# SCH_Pico_funboard_core3_2025-11-06.net
KiCad netlist of a schematic drawn in EasyEDA
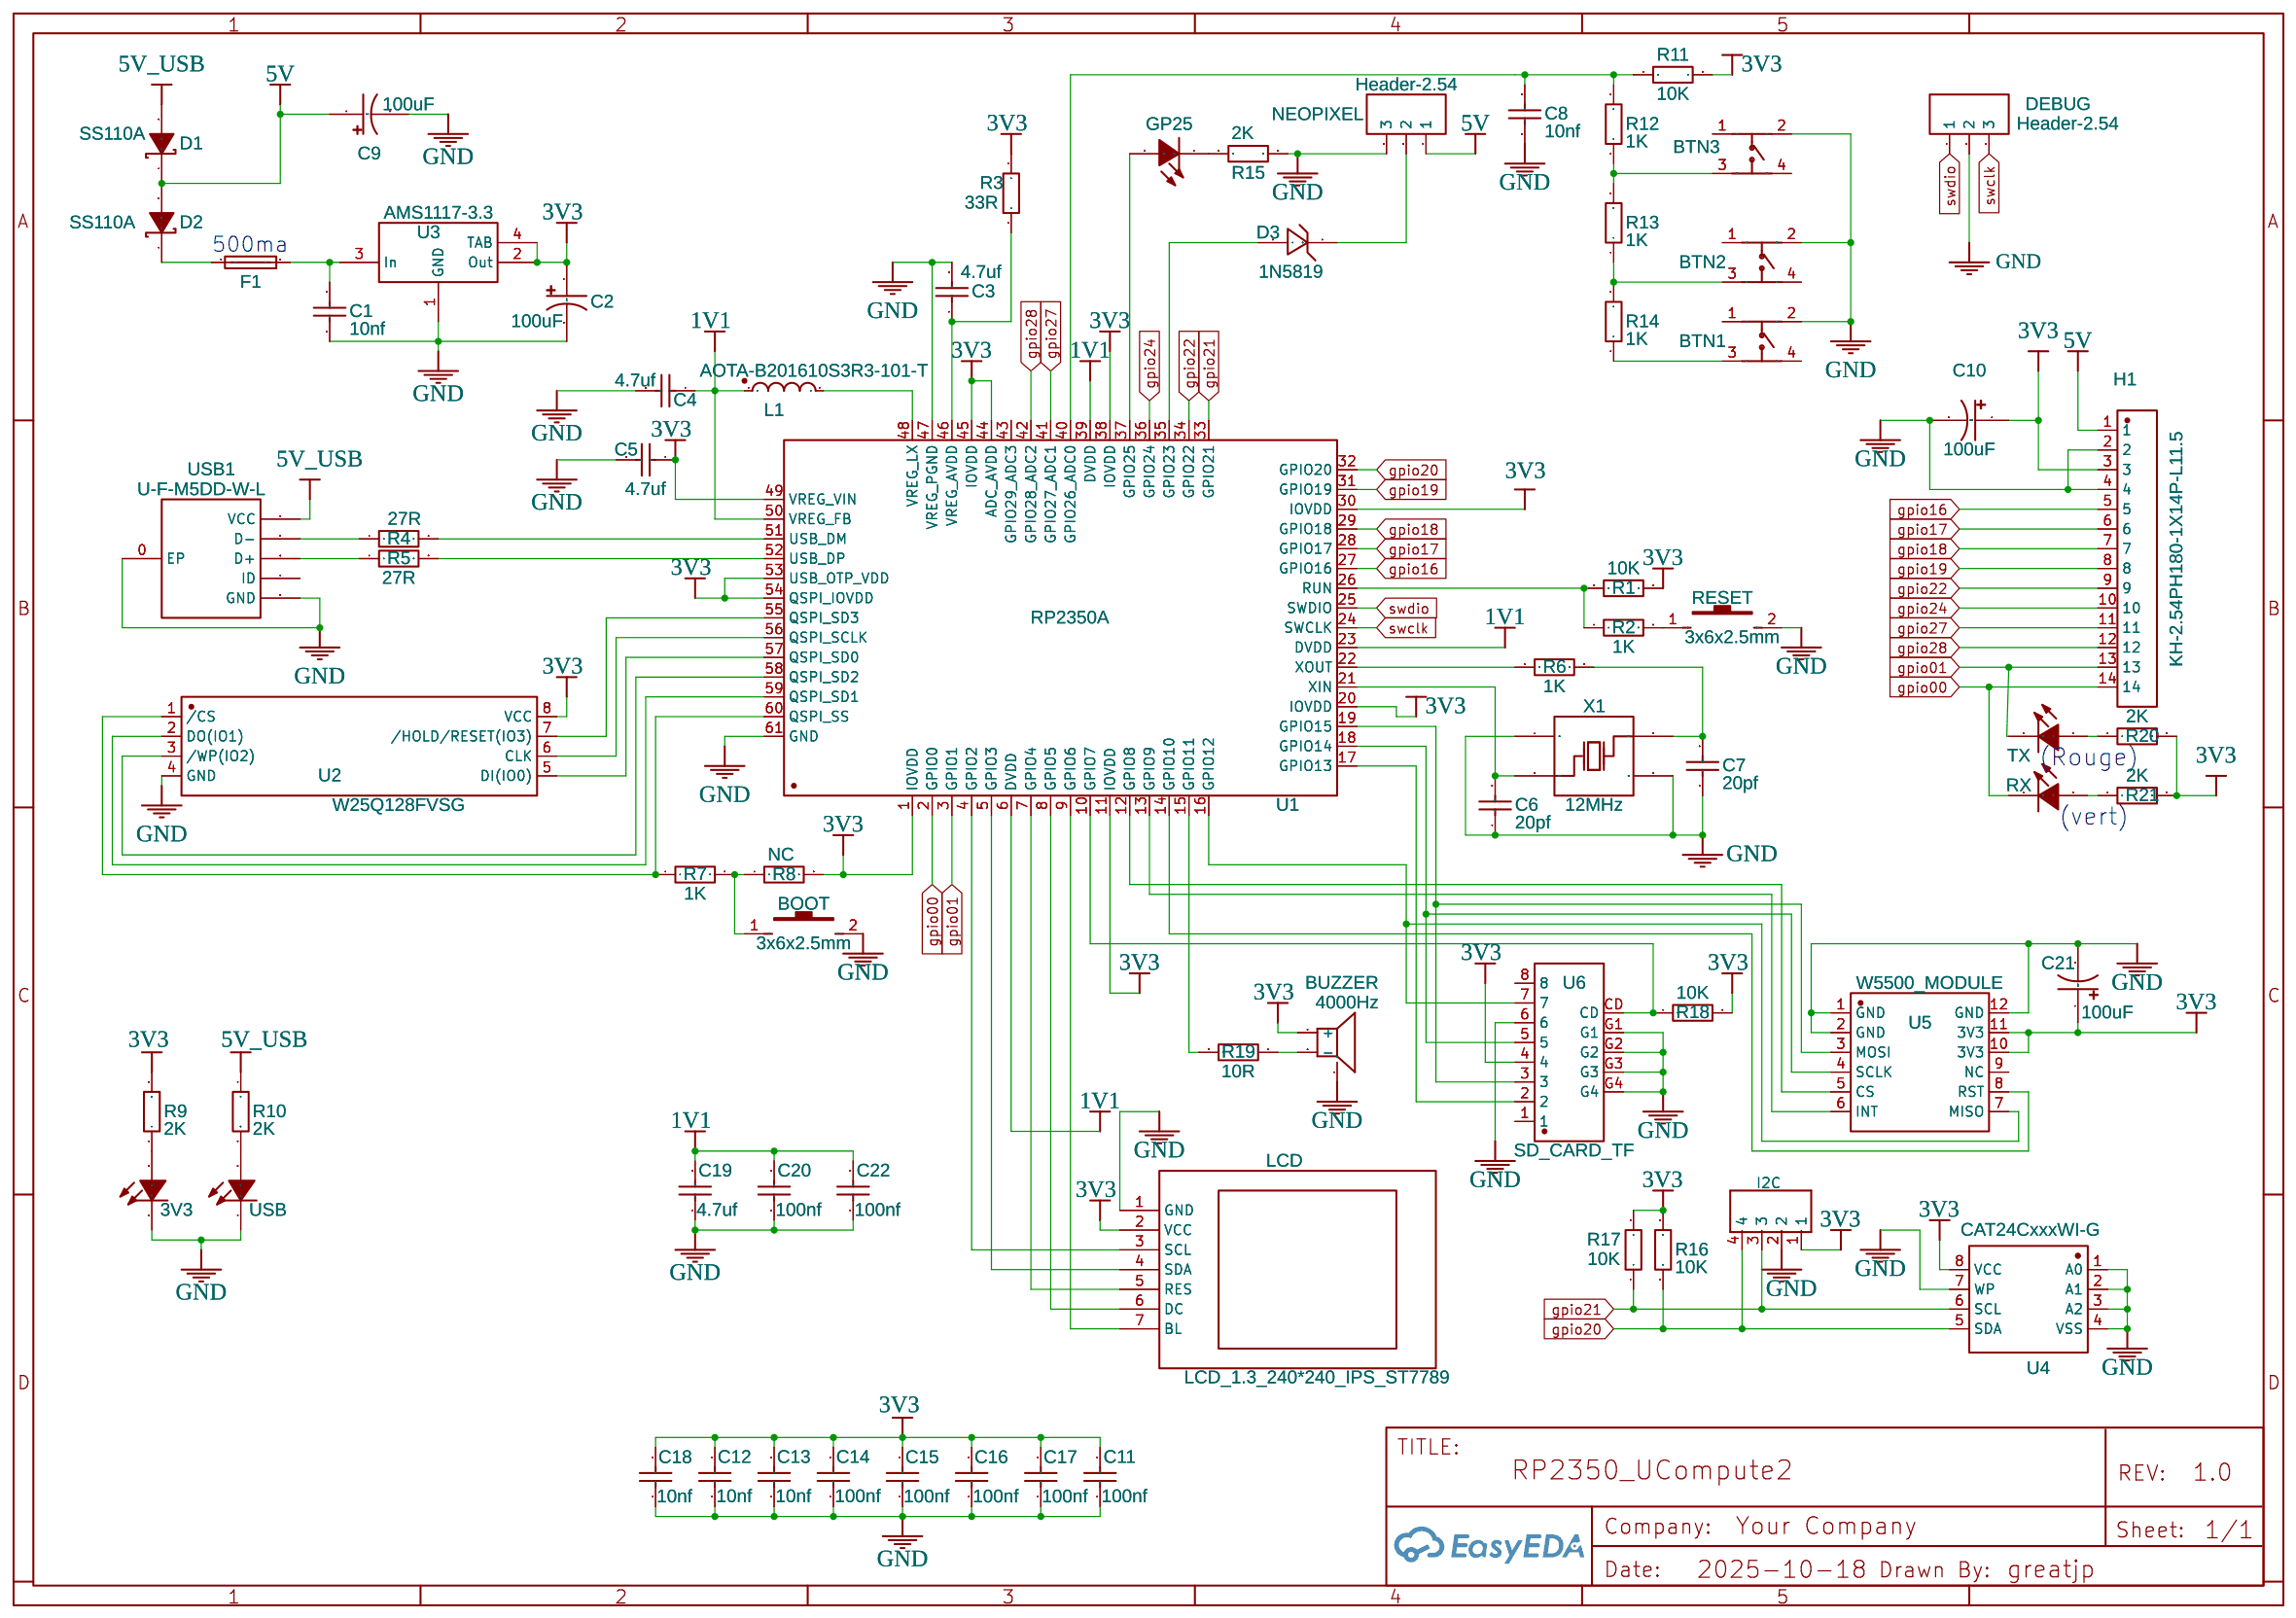
[diagram p0: schematic sheet]

(export (version "E")
  (design (tool "Eeschema 10.0.6"))
  (components
    (comp (ref "3V3")
      (value "XL-1206QPC")
      (fields (field (name "Manufacturer") "LCSC"))
      (libsource (lib "") (part "XL-1206QPC_1"))
    )
    (comp (ref "BOOT")
      (value "3x6x2.5mm")
      (fields (field (name "Manufacturer") "ReliaPro"))
      (libsource (lib "") (part "3x6x2.5mm"))
    )
    (comp (ref "BTN1")
      (value "TC-1102-A-J-R")
      (fields (field (name "Manufacturer") "XKB Connectivity(中国星坤)"))
      (libsource (lib "") (part "TC-1102-A-J-R"))
    )
    (comp (ref "BTN2")
      (value "TC-1102-A-J-R")
      (fields (field (name "Manufacturer") "XKB Connectivity(中国星坤)"))
      (libsource (lib "") (part "TC-1102-A-J-R"))
    )
    (comp (ref "BTN3")
      (value "TC-1102-A-J-R")
      (fields (field (name "Manufacturer") "XKB Connectivity(中国星坤)"))
      (libsource (lib "") (part "TC-1102-A-J-R"))
    )
    (comp (ref "BUZZER")
      (value "4000Hz")
      (fields (field (name "Manufacturer Part") "MLT-5030") (field (name "Manufacturer") "华能"))
      (libsource (lib "") (part "MLT-5030"))
    )
    (comp (ref "C1")
      (value "10nf")
      (fields (field (name "Manufacturer Part") "0805CG220J500NT") (field (name "Manufacturer") "FH"))
      (libsource (lib "") (part "0805CG220J500NT"))
    )
    (comp (ref "C2")
      (value "100uF")
      (fields
        (field (name "Manufacturer Part") "TLJA107M010R1400")
        (field (name "Manufacturer") "Kyocera AVX")
      )
      (libsource (lib "") (part "TLJA107M010R1400_1"))
    )
    (comp (ref "C3")
      (value "4.7uf")
      (fields (field (name "Manufacturer Part") "0805CG220J500NT") (field (name "Manufacturer") "FH"))
      (libsource (lib "") (part "0805CG220J500NT"))
    )
    (comp (ref "C4")
      (value "4.7uf")
      (fields (field (name "Manufacturer Part") "0805CG220J500NT") (field (name "Manufacturer") "FH"))
      (libsource (lib "") (part "0805CG220J500NT_1"))
    )
    (comp (ref "C5")
      (value "4.7uf")
      (fields (field (name "Manufacturer Part") "0805CG220J500NT") (field (name "Manufacturer") "FH"))
      (libsource (lib "") (part "0805CG220J500NT_1"))
    )
    (comp (ref "C6")
      (value "20pf")
      (fields (field (name "Manufacturer Part") "0805CG220J500NT") (field (name "Manufacturer") "FH"))
      (libsource (lib "") (part "0805CG220J500NT"))
    )
    (comp (ref "C7")
      (value "20pf")
      (fields (field (name "Manufacturer Part") "0805CG220J500NT") (field (name "Manufacturer") "FH"))
      (libsource (lib "") (part "0805CG220J500NT"))
    )
    (comp (ref "C8")
      (value "10nf")
      (fields (field (name "Manufacturer Part") "0805CG220J500NT") (field (name "Manufacturer") "FH"))
      (libsource (lib "") (part "0805CG220J500NT"))
    )
    (comp (ref "C9")
      (value "100uF")
      (fields
        (field (name "Manufacturer Part") "TLJA107M010R1400")
        (field (name "Manufacturer") "Kyocera AVX")
      )
      (libsource (lib "") (part "TLJA107M010R1400_3"))
    )
    (comp (ref "C10")
      (value "100uF")
      (fields
        (field (name "Manufacturer Part") "TLJA107M010R1400")
        (field (name "Manufacturer") "Kyocera AVX")
      )
      (libsource (lib "") (part "TLJA107M010R1400"))
    )
    (comp (ref "C11")
      (value "100nf")
      (fields (field (name "Manufacturer Part") "0805CG220J500NT") (field (name "Manufacturer") "FH"))
      (libsource (lib "") (part "0805CG220J500NT"))
    )
    (comp (ref "C12")
      (value "10nf")
      (fields (field (name "Manufacturer Part") "0805CG220J500NT") (field (name "Manufacturer") "FH"))
      (libsource (lib "") (part "0805CG220J500NT"))
    )
    (comp (ref "C13")
      (value "10nf")
      (fields (field (name "Manufacturer Part") "0805CG220J500NT") (field (name "Manufacturer") "FH"))
      (libsource (lib "") (part "0805CG220J500NT"))
    )
    (comp (ref "C14")
      (value "100nf")
      (fields (field (name "Manufacturer Part") "0805CG220J500NT") (field (name "Manufacturer") "FH"))
      (libsource (lib "") (part "0805CG220J500NT"))
    )
    (comp (ref "C15")
      (value "100nf")
      (fields (field (name "Manufacturer Part") "0805CG220J500NT") (field (name "Manufacturer") "FH"))
      (libsource (lib "") (part "0805CG220J500NT"))
    )
    (comp (ref "C16")
      (value "100nf")
      (fields (field (name "Manufacturer Part") "0805CG220J500NT") (field (name "Manufacturer") "FH"))
      (libsource (lib "") (part "0805CG220J500NT"))
    )
    (comp (ref "C17")
      (value "100nf")
      (fields (field (name "Manufacturer Part") "0805CG220J500NT") (field (name "Manufacturer") "FH"))
      (libsource (lib "") (part "0805CG220J500NT"))
    )
    (comp (ref "C18")
      (value "10nf")
      (fields (field (name "Manufacturer Part") "0805CG220J500NT") (field (name "Manufacturer") "FH"))
      (libsource (lib "") (part "0805CG220J500NT"))
    )
    (comp (ref "C19")
      (value "4.7uf")
      (fields (field (name "Manufacturer Part") "0805CG220J500NT") (field (name "Manufacturer") "FH"))
      (libsource (lib "") (part "0805CG220J500NT"))
    )
    (comp (ref "C20")
      (value "100nf")
      (fields (field (name "Manufacturer Part") "0805CG220J500NT") (field (name "Manufacturer") "FH"))
      (libsource (lib "") (part "0805CG220J500NT"))
    )
    (comp (ref "C21")
      (value "100uF")
      (fields
        (field (name "Manufacturer Part") "TLJA107M010R1400")
        (field (name "Manufacturer") "Kyocera AVX")
      )
      (libsource (lib "") (part "TLJA107M010R1400_2"))
    )
    (comp (ref "C22")
      (value "100nf")
      (fields (field (name "Manufacturer Part") "0805CG220J500NT") (field (name "Manufacturer") "FH"))
      (libsource (lib "") (part "0805CG220J500NT"))
    )
    (comp (ref "D1")
      (value "SS110A")
      (fields (field (name "Manufacturer") "Yangzhou Yangjie Elec Tech"))
      (libsource (lib "") (part "SS110A"))
    )
    (comp (ref "D2")
      (value "SS110A")
      (fields (field (name "Manufacturer") "Yangzhou Yangjie Elec Tech"))
      (libsource (lib "") (part "SS110A"))
    )
    (comp (ref "D3")
      (value "1N5819")
      (fields (field (name "Manufacturer Part") "1N4148D"))
      (libsource (lib "") (part "1N4148D"))
    )
    (comp (ref "DEBUG")
      (value "Header-2.54")
      (fields (field (name "Manufacturer Part") "2.54-1*3P针") (field (name "Manufacturer") "BOOMELE(博穆精密)"))
      (libsource (lib "") (part "Header-Male-2.54_1x3_1"))
    )
    (comp (ref "F1")
      (value "FUSE1206")
      (fields (field (name "Manufacturer Part") "D22051903536_fuse1206"))
      (libsource (lib "") (part "D22051903536_FUSE1206"))
    )
    (comp (ref "GP25")
      (value "XL-1206QPC")
      (fields (field (name "Manufacturer") "LCSC"))
      (libsource (lib "") (part "XL-1206QPC_3"))
    )
    (comp (ref "H1")
      (value "KH-2.54PH180-1X14P-L11.5")
      (fields (field (name "Manufacturer") "kinghelm(金航标)"))
      (libsource (lib "") (part "KH-2.54PH180-1X14P-L11.5"))
    )
    (comp (ref "I2C") (value "I2C") (libsource (lib "") (part "Unknown_890_-201")))
    (comp (ref "L1")
      (value "AOTA-B201610S3R3-101-T")
      (fields (field (name "Manufacturer") "ABRACON"))
      (libsource (lib "") (part "AOTA-B201610S3R3-101-T"))
    )
    (comp (ref "LCD")
      (value "LCD_1.3_240*240_IPS_ST7789")
      (libsource (lib "") (part "LCD_1.3_240*240_IPS_ST7789"))
    )
    (comp (ref "NEOPIXEL")
      (value "Header-2.54")
      (fields (field (name "Manufacturer Part") "2.54-1*3P针") (field (name "Manufacturer") "BOOMELE(博穆精密)"))
      (libsource (lib "") (part "Header-Male-2.54_1x3"))
    )
    (comp (ref "R1")
      (value "10K")
      (fields (field (name "Manufacturer Part") "RC0805DR-071KL") (field (name "Manufacturer") "YAGEO(国巨)"))
      (libsource (lib "") (part "RC0805DR-071KL"))
    )
    (comp (ref "R2")
      (value "1K")
      (fields (field (name "Manufacturer Part") "RC0805DR-071KL") (field (name "Manufacturer") "YAGEO(国巨)"))
      (libsource (lib "") (part "RC0805DR-071KL"))
    )
    (comp (ref "R3")
      (value "33R")
      (fields (field (name "Manufacturer Part") "RC0805DR-071KL") (field (name "Manufacturer") "YAGEO(国巨)"))
      (libsource (lib "") (part "RC0805DR-071KL_1"))
    )
    (comp (ref "R4")
      (value "27R")
      (fields (field (name "Manufacturer Part") "RC0805DR-071KL") (field (name "Manufacturer") "YAGEO(国巨)"))
      (libsource (lib "") (part "RC0805DR-071KL"))
    )
    (comp (ref "R5")
      (value "27R")
      (fields (field (name "Manufacturer Part") "RC0805DR-071KL") (field (name "Manufacturer") "YAGEO(国巨)"))
      (libsource (lib "") (part "RC0805DR-071KL"))
    )
    (comp (ref "R6")
      (value "1K")
      (fields (field (name "Manufacturer Part") "RC0805DR-071KL") (field (name "Manufacturer") "YAGEO(国巨)"))
      (libsource (lib "") (part "RC0805DR-071KL"))
    )
    (comp (ref "R7")
      (value "1K")
      (fields (field (name "Manufacturer Part") "RC0805DR-071KL") (field (name "Manufacturer") "YAGEO(国巨)"))
      (libsource (lib "") (part "RC0805DR-071KL"))
    )
    (comp (ref "R8")
      (value "NC")
      (fields (field (name "Manufacturer Part") "RC0805DR-071KL") (field (name "Manufacturer") "YAGEO(国巨)"))
      (libsource (lib "") (part "RC0805DR-071KL"))
    )
    (comp (ref "R9")
      (value "2K")
      (fields (field (name "Manufacturer Part") "RC0805DR-071KL") (field (name "Manufacturer") "YAGEO(国巨)"))
      (libsource (lib "") (part "RC0805DR-071KL_1"))
    )
    (comp (ref "R10")
      (value "2K")
      (fields (field (name "Manufacturer Part") "RC0805DR-071KL") (field (name "Manufacturer") "YAGEO(国巨)"))
      (libsource (lib "") (part "RC0805DR-071KL_2"))
    )
    (comp (ref "R11")
      (value "10K")
      (fields (field (name "Manufacturer Part") "RC0805DR-071KL") (field (name "Manufacturer") "YAGEO(国巨)"))
      (libsource (lib "") (part "RC0805DR-071KL"))
    )
    (comp (ref "R12")
      (value "1K")
      (fields (field (name "Manufacturer Part") "RC0805DR-071KL") (field (name "Manufacturer") "YAGEO(国巨)"))
      (libsource (lib "") (part "RC0805DR-071KL_1"))
    )
    (comp (ref "R13")
      (value "1K")
      (fields (field (name "Manufacturer Part") "RC0805DR-071KL") (field (name "Manufacturer") "YAGEO(国巨)"))
      (libsource (lib "") (part "RC0805DR-071KL_1"))
    )
    (comp (ref "R14")
      (value "1K")
      (fields (field (name "Manufacturer Part") "RC0805DR-071KL") (field (name "Manufacturer") "YAGEO(国巨)"))
      (libsource (lib "") (part "RC0805DR-071KL_1"))
    )
    (comp (ref "R15")
      (value "2K")
      (fields (field (name "Manufacturer Part") "RC0805DR-071KL") (field (name "Manufacturer") "YAGEO(国巨)"))
      (libsource (lib "") (part "RC0805DR-071KL"))
    )
    (comp (ref "R16")
      (value "10K")
      (fields (field (name "Manufacturer Part") "RC0805DR-071KL") (field (name "Manufacturer") "YAGEO(国巨)"))
      (libsource (lib "") (part "RC0805DR-071KL_1"))
    )
    (comp (ref "R17")
      (value "10K")
      (fields (field (name "Manufacturer Part") "RC0805DR-071KL") (field (name "Manufacturer") "YAGEO(国巨)"))
      (libsource (lib "") (part "RC0805DR-071KL_1"))
    )
    (comp (ref "R18")
      (value "10K")
      (fields (field (name "Manufacturer Part") "RC0805DR-071KL") (field (name "Manufacturer") "YAGEO(国巨)"))
      (libsource (lib "") (part "RC0805DR-071KL"))
    )
    (comp (ref "R19")
      (value "10R")
      (fields (field (name "Manufacturer Part") "RC0805DR-071KL") (field (name "Manufacturer") "YAGEO(国巨)"))
      (libsource (lib "") (part "RC0805DR-071KL_3"))
    )
    (comp (ref "R20")
      (value "2K")
      (fields (field (name "Manufacturer Part") "RC0805DR-071KL") (field (name "Manufacturer") "YAGEO(国巨)"))
      (libsource (lib "") (part "RC0805DR-071KL"))
    )
    (comp (ref "R21")
      (value "2K")
      (fields (field (name "Manufacturer Part") "RC0805DR-071KL") (field (name "Manufacturer") "YAGEO(国巨)"))
      (libsource (lib "") (part "RC0805DR-071KL"))
    )
    (comp (ref "RESET")
      (value "3x6x2.5mm")
      (fields (field (name "Manufacturer") "ReliaPro"))
      (libsource (lib "") (part "3x6x2.5mm_1"))
    )
    (comp (ref "RX1")
      (value "RX")
      (fields (field (name "Manufacturer Part") "XL-1206QPC") (field (name "Manufacturer") "LCSC"))
      (libsource (lib "") (part "XL-1206QPC"))
    )
    (comp (ref "TX1")
      (value "TX")
      (fields (field (name "Manufacturer Part") "XL-1206QPC") (field (name "Manufacturer") "LCSC"))
      (libsource (lib "") (part "XL-1206QPC_2"))
    )
    (comp (ref "U1")
      (value "RP2350A")
      (fields (field (name "Manufacturer") "Raspberry Pi(树莓派)"))
      (libsource (lib "") (part "RP2350A_C42411118"))
    )
    (comp (ref "U2") (value "W25Q128FVSG") (libsource (lib "") (part "W25Q128FVSG")))
    (comp (ref "U3")
      (value "AMS1117-3.3")
      (fields (field (name "Manufacturer Part") "AMS1117-5.0") (field (name "Manufacturer") "SK"))
      (libsource (lib "") (part "AMS1117-5.0_C165483"))
    )
    (comp (ref "U4") (value "CAT24CxxxWI-G") (libsource (lib "") (part "CAT24C256WI-G")))
    (comp (ref "U5") (value "W5500_MODULE") (libsource (lib "") (part "W5500_MODULE")))
    (comp (ref "U6")
      (value "SD_CARD_TF")
      (fields (field (name "Manufacturer Part") "SD_Card_TF"))
      (libsource (lib "") (part "SD_CARD_TF"))
    )
    (comp (ref "USB")
      (value "XL-1206QPC")
      (fields (field (name "Manufacturer") "LCSC"))
      (libsource (lib "") (part "XL-1206QPC_4"))
    )
    (comp (ref "USB1")
      (value "U-F-M5DD-W-L")
      (fields (field (name "Manufacturer") "韩国韩荣"))
      (libsource (lib "") (part "U-F-M5DD-W-L"))
    )
    (comp (ref "X1")
      (value "12MHz")
      (fields
        (field (name "Manufacturer Part") "TSX-3225 12MHz 20pF 30ppm")
        (field (name "Manufacturer") "EPSON")
      )
      (libsource (lib "") (part "TSX-3225 12MHz 20pF 30ppm"))
    )
  )
  (nets
    (net (code "1") (name "1V1") (class "Default")
      (node (ref "C19") (pin "2") (pinfunction "2_2") (pintype "input"))
      (node (ref "C20") (pin "2") (pinfunction "2_2") (pintype "input"))
      (node (ref "C22") (pin "2") (pinfunction "2_2") (pintype "input"))
      (node (ref "C4") (pin "1") (pinfunction "1_1") (pintype "input"))
      (node (ref "L1") (pin "2") (pinfunction "2_2") (pintype "unspecified"))
      (node (ref "U1") (pin "23") (pinfunction "DVDD_23") (pintype "unspecified"))
      (node (ref "U1") (pin "39") (pinfunction "DVDD_39") (pintype "unspecified"))
      (node (ref "U1") (pin "50") (pinfunction "VREG_FB_50") (pintype "unspecified"))
      (node (ref "U1") (pin "6") (pinfunction "DVDD_6") (pintype "unspecified"))
    )
    (net (code "2") (name "3V3") (class "Default")
      (node (ref "BUZZER") (pin "2") (pinfunction "+_2") (pintype "unspecified"))
      (node (ref "C10") (pin "1") (pinfunction "1_1") (pintype "unspecified"))
      (node (ref "C11") (pin "2") (pinfunction "2_2") (pintype "input"))
      (node (ref "C12") (pin "2") (pinfunction "2_2") (pintype "input"))
      (node (ref "C13") (pin "2") (pinfunction "2_2") (pintype "input"))
      (node (ref "C14") (pin "2") (pinfunction "2_2") (pintype "input"))
      (node (ref "C15") (pin "2") (pinfunction "2_2") (pintype "input"))
      (node (ref "C16") (pin "2") (pinfunction "2_2") (pintype "input"))
      (node (ref "C17") (pin "2") (pinfunction "2_2") (pintype "input"))
      (node (ref "C18") (pin "2") (pinfunction "2_2") (pintype "input"))
      (node (ref "C2") (pin "1") (pinfunction "1_1") (pintype "unspecified"))
      (node (ref "C21") (pin "1") (pinfunction "1_1") (pintype "unspecified"))
      (node (ref "C5") (pin "1") (pinfunction "1_1") (pintype "input"))
      (node (ref "H1") (pin "3") (pinfunction "3_3") (pintype "unspecified"))
      (node (ref "I2C") (pin "1") (pinfunction "1_1") (pintype "bidirectional"))
      (node (ref "LCD") (pin "2") (pinfunction "VCC_2") (pintype "unspecified"))
      (node (ref "R1") (pin "2") (pinfunction "2_2") (pintype "unspecified"))
      (node (ref "R11") (pin "2") (pinfunction "2_2") (pintype "unspecified"))
      (node (ref "R16") (pin "2") (pinfunction "2_2") (pintype "unspecified"))
      (node (ref "R17") (pin "2") (pinfunction "2_2") (pintype "unspecified"))
      (node (ref "R18") (pin "2") (pinfunction "2_2") (pintype "unspecified"))
      (node (ref "R20") (pin "2") (pinfunction "2_2") (pintype "unspecified"))
      (node (ref "R21") (pin "2") (pinfunction "2_2") (pintype "unspecified"))
      (node (ref "R3") (pin "2") (pinfunction "2_2") (pintype "unspecified"))
      (node (ref "R8") (pin "2") (pinfunction "2_2") (pintype "unspecified"))
      (node (ref "R9") (pin "2") (pinfunction "2_2") (pintype "unspecified"))
      (node (ref "U1") (pin "1") (pinfunction "IOVDD_1") (pintype "unspecified"))
      (node (ref "U1") (pin "11") (pinfunction "IOVDD_11") (pintype "unspecified"))
      (node (ref "U1") (pin "20") (pinfunction "IOVDD_20") (pintype "unspecified"))
      (node (ref "U1") (pin "30") (pinfunction "IOVDD_30") (pintype "unspecified"))
      (node (ref "U1") (pin "38") (pinfunction "IOVDD_38") (pintype "unspecified"))
      (node (ref "U1") (pin "44") (pinfunction "ADC_AVDD_44") (pintype "unspecified"))
      (node (ref "U1") (pin "45") (pinfunction "IOVDD_45") (pintype "unspecified"))
      (node (ref "U1") (pin "49") (pinfunction "VREG_VIN_49") (pintype "unspecified"))
      (node (ref "U1") (pin "53") (pinfunction "USB_OTP_VDD_53") (pintype "unspecified"))
      (node (ref "U1") (pin "54") (pinfunction "QSPI_IOVDD_54") (pintype "unspecified"))
      (node (ref "U2") (pin "8") (pinfunction "VCC_8") (pintype "unspecified"))
      (node (ref "U3") (pin "2") (pinfunction "Out_2") (pintype "unspecified"))
      (node (ref "U3") (pin "4") (pinfunction "TAB_4") (pintype "unspecified"))
      (node (ref "U4") (pin "8") (pinfunction "VCC_8") (pintype "unspecified"))
      (node (ref "U5") (pin "10") (pinfunction "3V3_10") (pintype "unspecified"))
      (node (ref "U5") (pin "11") (pinfunction "3V3_11") (pintype "unspecified"))
      (node (ref "U6") (pin "4") (pinfunction "4_4") (pintype "unspecified"))
    )
    (net (code "3") (name "5V") (class "Default")
      (node (ref "C9") (pin "1") (pinfunction "1_1") (pintype "unspecified"))
      (node (ref "D1") (pin "2") (pinfunction "A_2") (pintype "unspecified"))
      (node (ref "D2") (pin "1") (pinfunction "K_1") (pintype "unspecified"))
      (node (ref "H1") (pin "1") (pinfunction "1_1") (pintype "unspecified"))
      (node (ref "NEOPIXEL") (pin "1") (pinfunction "1_1") (pintype "input"))
    )
    (net (code "4") (name "5V_USB") (class "Default")
      (node (ref "D2") (pin "2") (pinfunction "A_2") (pintype "unspecified"))
      (node (ref "R10") (pin "1") (pinfunction "1_1") (pintype "unspecified"))
      (node (ref "USB1") (pin "1") (pinfunction "VCC_1") (pintype "input"))
    )
    (net (code "5") (name "GND") (class "Default")
      (node (ref "3V3") (pin "1") (pinfunction "K_1") (pintype "unspecified"))
      (node (ref "BOOT") (pin "2") (pinfunction "2_2") (pintype "input"))
      (node (ref "BTN1") (pin "2") (pinfunction "2_2") (pintype "unspecified"))
      (node (ref "BTN2") (pin "2") (pinfunction "2_2") (pintype "unspecified"))
      (node (ref "BTN3") (pin "2") (pinfunction "2_2") (pintype "unspecified"))
      (node (ref "BUZZER") (pin "1") (pinfunction "NC_1") (pintype "unspecified"))
      (node (ref "C1") (pin "1") (pinfunction "1_1") (pintype "input"))
      (node (ref "C10") (pin "2") (pinfunction "2_2") (pintype "unspecified"))
      (node (ref "C11") (pin "1") (pinfunction "1_1") (pintype "input"))
      (node (ref "C12") (pin "1") (pinfunction "1_1") (pintype "input"))
      (node (ref "C13") (pin "1") (pinfunction "1_1") (pintype "input"))
      (node (ref "C14") (pin "1") (pinfunction "1_1") (pintype "input"))
      (node (ref "C15") (pin "1") (pinfunction "1_1") (pintype "input"))
      (node (ref "C16") (pin "1") (pinfunction "1_1") (pintype "input"))
      (node (ref "C17") (pin "1") (pinfunction "1_1") (pintype "input"))
      (node (ref "C18") (pin "1") (pinfunction "1_1") (pintype "input"))
      (node (ref "C19") (pin "1") (pinfunction "1_1") (pintype "input"))
      (node (ref "C2") (pin "2") (pinfunction "2_2") (pintype "unspecified"))
      (node (ref "C20") (pin "1") (pinfunction "1_1") (pintype "input"))
      (node (ref "C21") (pin "2") (pinfunction "2_2") (pintype "unspecified"))
      (node (ref "C22") (pin "1") (pinfunction "1_1") (pintype "input"))
      (node (ref "C3") (pin "2") (pinfunction "2_2") (pintype "input"))
      (node (ref "C4") (pin "2") (pinfunction "2_2") (pintype "input"))
      (node (ref "C5") (pin "2") (pinfunction "2_2") (pintype "input"))
      (node (ref "C6") (pin "1") (pinfunction "1_1") (pintype "input"))
      (node (ref "C7") (pin "1") (pinfunction "1_1") (pintype "input"))
      (node (ref "C8") (pin "1") (pinfunction "1_1") (pintype "input"))
      (node (ref "C9") (pin "2") (pinfunction "2_2") (pintype "unspecified"))
      (node (ref "DEBUG") (pin "2") (pinfunction "2_2") (pintype "input"))
      (node (ref "H1") (pin "2") (pinfunction "2_2") (pintype "unspecified"))
      (node (ref "H1") (pin "4") (pinfunction "4_4") (pintype "unspecified"))
      (node (ref "I2C") (pin "2") (pinfunction "2_2") (pintype "bidirectional"))
      (node (ref "LCD") (pin "1") (pinfunction "GND_1") (pintype "unspecified"))
      (node (ref "NEOPIXEL") (pin "3") (pinfunction "3_3") (pintype "input"))
      (node (ref "R15") (pin "2") (pinfunction "2_2") (pintype "unspecified"))
      (node (ref "RESET") (pin "2") (pinfunction "2_2") (pintype "input"))
      (node (ref "U1") (pin "47") (pinfunction "VREG_PGND_47") (pintype "unspecified"))
      (node (ref "U1") (pin "61") (pinfunction "GND_61") (pintype "unspecified"))
      (node (ref "U2") (pin "4") (pinfunction "GND_4") (pintype "unspecified"))
      (node (ref "U3") (pin "1") (pinfunction "GND_1") (pintype "unspecified"))
      (node (ref "U4") (pin "1") (pinfunction "A0_1") (pintype "unspecified"))
      (node (ref "U4") (pin "2") (pinfunction "A1_2") (pintype "unspecified"))
      (node (ref "U4") (pin "3") (pinfunction "A2_3") (pintype "unspecified"))
      (node (ref "U4") (pin "4") (pinfunction "VSS_4") (pintype "unspecified"))
      (node (ref "U4") (pin "7") (pinfunction "WP_7") (pintype "unspecified"))
      (node (ref "U5") (pin "1") (pinfunction "GND_1") (pintype "unspecified"))
      (node (ref "U5") (pin "12") (pinfunction "GND_12") (pintype "unspecified"))
      (node (ref "U5") (pin "2") (pinfunction "GND_2") (pintype "unspecified"))
      (node (ref "U6") (pin "6") (pinfunction "6_6") (pintype "unspecified"))
      (node (ref "U6") (pin "G1") (pinfunction "G1_G1") (pintype "unspecified"))
      (node (ref "U6") (pin "G2") (pinfunction "G2_G2") (pintype "unspecified"))
      (node (ref "U6") (pin "G3") (pinfunction "G3_G3") (pintype "unspecified"))
      (node (ref "U6") (pin "G4") (pinfunction "G4_G4") (pintype "unspecified"))
      (node (ref "USB") (pin "1") (pinfunction "K_1") (pintype "unspecified"))
      (node (ref "USB1") (pin "0") (pinfunction "EP_0") (pintype "unspecified"))
      (node (ref "USB1") (pin "5") (pinfunction "GND_5") (pintype "input"))
      (node (ref "X1") (pin "2") (pinfunction "NC_2") (pintype "input"))
      (node (ref "X1") (pin "4") (pinfunction "NC_4") (pintype "input"))
    )
    (net (code "6") (name "Net-(3V3-A)") (class "Default")
      (node (ref "3V3") (pin "2") (pinfunction "A_2") (pintype "unspecified"))
      (node (ref "R9") (pin "1") (pinfunction "1_1") (pintype "unspecified"))
    )
    (net (code "7") (name "Net-(BOOT-Pad1)") (class "Default")
      (node (ref "BOOT") (pin "1") (pinfunction "1_1") (pintype "input"))
      (node (ref "R7") (pin "2") (pinfunction "2_2") (pintype "unspecified"))
      (node (ref "R8") (pin "1") (pinfunction "1_1") (pintype "unspecified"))
    )
    (net (code "8") (name "Net-(BTN1-Pad3)") (class "Default")
      (node (ref "BTN1") (pin "3") (pinfunction "3_3") (pintype "unspecified"))
      (node (ref "R14") (pin "1") (pinfunction "1_1") (pintype "unspecified"))
    )
    (net (code "9") (name "Net-(BTN2-Pad3)") (class "Default")
      (node (ref "BTN2") (pin "3") (pinfunction "3_3") (pintype "unspecified"))
      (node (ref "R13") (pin "1") (pinfunction "1_1") (pintype "unspecified"))
      (node (ref "R14") (pin "2") (pinfunction "2_2") (pintype "unspecified"))
    )
    (net (code "10") (name "Net-(BTN3-Pad3)") (class "Default")
      (node (ref "BTN3") (pin "3") (pinfunction "3_3") (pintype "unspecified"))
      (node (ref "R12") (pin "1") (pinfunction "1_1") (pintype "unspecified"))
      (node (ref "R13") (pin "2") (pinfunction "2_2") (pintype "unspecified"))
    )
    (net (code "11") (name "Net-(BUZZER--)") (class "Default")
      (node (ref "BUZZER") (pin "3") (pinfunction "-_3") (pintype "unspecified"))
      (node (ref "R19") (pin "1") (pinfunction "1_1") (pintype "unspecified"))
    )
    (net (code "12") (name "Net-(D1-K)") (class "Default")
      (node (ref "D1") (pin "1") (pinfunction "K_1") (pintype "unspecified"))
      (node (ref "F1") (pin "1") (pinfunction "1_1") (pintype "unspecified"))
    )
    (net (code "13") (name "Net-(D3-A)") (class "Default")
      (node (ref "D3") (pin "2") (pinfunction "A_2") (pintype "unspecified"))
      (node (ref "U1") (pin "35") (pinfunction "GPIO23_35") (pintype "unspecified"))
    )
    (net (code "14") (name "Net-(D3-C)") (class "Default")
      (node (ref "D3") (pin "1") (pinfunction "C_1") (pintype "unspecified"))
      (node (ref "NEOPIXEL") (pin "2") (pinfunction "2_2") (pintype "input"))
    )
    (net (code "15") (name "Net-(GP25-A)") (class "Default")
      (node (ref "GP25") (pin "2") (pinfunction "A_2") (pintype "unspecified"))
      (node (ref "U1") (pin "37") (pinfunction "GPIO25_37") (pintype "unspecified"))
    )
    (net (code "16") (name "Net-(GP25-K)") (class "Default")
      (node (ref "GP25") (pin "1") (pinfunction "K_1") (pintype "unspecified"))
      (node (ref "R15") (pin "1") (pinfunction "1_1") (pintype "unspecified"))
    )
    (net (code "17") (name "Net-(LCD-BL)") (class "Default")
      (node (ref "LCD") (pin "7") (pinfunction "BL_7") (pintype "unspecified"))
      (node (ref "U1") (pin "9") (pinfunction "GPIO6_9") (pintype "unspecified"))
    )
    (net (code "18") (name "Net-(LCD-DC)") (class "Default")
      (node (ref "LCD") (pin "6") (pinfunction "DC_6") (pintype "unspecified"))
      (node (ref "U1") (pin "8") (pinfunction "GPIO5_8") (pintype "unspecified"))
    )
    (net (code "19") (name "Net-(LCD-RES)") (class "Default")
      (node (ref "LCD") (pin "5") (pinfunction "RES_5") (pintype "unspecified"))
      (node (ref "U1") (pin "7") (pinfunction "GPIO4_7") (pintype "unspecified"))
    )
    (net (code "20") (name "Net-(LCD-SCL)") (class "Default")
      (node (ref "LCD") (pin "3") (pinfunction "SCL_3") (pintype "unspecified"))
      (node (ref "U1") (pin "4") (pinfunction "GPIO2_4") (pintype "unspecified"))
    )
    (net (code "21") (name "Net-(LCD-SDA)") (class "Default")
      (node (ref "LCD") (pin "4") (pinfunction "SDA_4") (pintype "unspecified"))
      (node (ref "U1") (pin "5") (pinfunction "GPIO3_5") (pintype "unspecified"))
    )
    (net (code "22") (name "Net-(R2-Pad2)") (class "Default")
      (node (ref "R2") (pin "2") (pinfunction "2_2") (pintype "unspecified"))
      (node (ref "RESET") (pin "1") (pinfunction "1_1") (pintype "input"))
    )
    (net (code "23") (name "Net-(RX1-A)") (class "Default")
      (node (ref "R21") (pin "1") (pinfunction "1_1") (pintype "unspecified"))
      (node (ref "RX1") (pin "2") (pinfunction "A_2") (pintype "unspecified"))
    )
    (net (code "24") (name "Net-(TX1-A)") (class "Default")
      (node (ref "R20") (pin "1") (pinfunction "1_1") (pintype "unspecified"))
      (node (ref "TX1") (pin "2") (pinfunction "A_2") (pintype "unspecified"))
    )
    (net (code "25") (name "Net-(U1-GPIO7)") (class "Default")
      (node (ref "R18") (pin "1") (pinfunction "1_1") (pintype "unspecified"))
      (node (ref "U1") (pin "10") (pinfunction "GPIO7_10") (pintype "unspecified"))
      (node (ref "U6") (pin "CD") (pinfunction "CD_CD") (pintype "unspecified"))
    )
    (net (code "26") (name "Net-(U1-GPIO8)") (class "Default")
      (node (ref "U1") (pin "12") (pinfunction "GPIO8_12") (pintype "unspecified"))
      (node (ref "U5") (pin "5") (pinfunction "CS_5") (pintype "unspecified"))
    )
    (net (code "27") (name "Net-(U1-GPIO9)") (class "Default")
      (node (ref "U1") (pin "13") (pinfunction "GPIO9_13") (pintype "unspecified"))
      (node (ref "U5") (pin "6") (pinfunction "INT_6") (pintype "unspecified"))
    )
    (net (code "28") (name "Net-(U1-GPIO10)") (class "Default")
      (node (ref "U1") (pin "14") (pinfunction "GPIO10_14") (pintype "unspecified"))
      (node (ref "U5") (pin "8") (pinfunction "RST_8") (pintype "unspecified"))
    )
    (net (code "29") (name "Net-(U1-GPIO11)") (class "Default")
      (node (ref "R19") (pin "2") (pinfunction "2_2") (pintype "unspecified"))
      (node (ref "U1") (pin "15") (pinfunction "GPIO11_15") (pintype "unspecified"))
    )
    (net (code "30") (name "Net-(U1-GPIO12)") (class "Default")
      (node (ref "U1") (pin "16") (pinfunction "GPIO12_16") (pintype "unspecified"))
      (node (ref "U5") (pin "7") (pinfunction "MISO_7") (pintype "unspecified"))
      (node (ref "U6") (pin "7") (pinfunction "7_7") (pintype "unspecified"))
    )
    (net (code "31") (name "Net-(U1-GPIO13)") (class "Default")
      (node (ref "U1") (pin "17") (pinfunction "GPIO13_17") (pintype "unspecified"))
      (node (ref "U6") (pin "2") (pinfunction "2_2") (pintype "unspecified"))
    )
    (net (code "32") (name "Net-(U1-GPIO14)") (class "Default")
      (node (ref "U1") (pin "18") (pinfunction "GPIO14_18") (pintype "unspecified"))
      (node (ref "U5") (pin "4") (pinfunction "SCLK_4") (pintype "unspecified"))
      (node (ref "U6") (pin "5") (pinfunction "5_5") (pintype "unspecified"))
    )
    (net (code "33") (name "Net-(U1-GPIO15)") (class "Default")
      (node (ref "U1") (pin "19") (pinfunction "GPIO15_19") (pintype "unspecified"))
      (node (ref "U5") (pin "3") (pinfunction "MOSI_3") (pintype "unspecified"))
      (node (ref "U6") (pin "3") (pinfunction "3_3") (pintype "unspecified"))
    )
    (net (code "34") (name "Net-(U1-GPIO26_ADC0)") (class "Default")
      (node (ref "C8") (pin "2") (pinfunction "2_2") (pintype "input"))
      (node (ref "R11") (pin "1") (pinfunction "1_1") (pintype "unspecified"))
      (node (ref "R12") (pin "2") (pinfunction "2_2") (pintype "unspecified"))
      (node (ref "U1") (pin "40") (pinfunction "GPIO26_ADC0_40") (pintype "unspecified"))
    )
    (net (code "35") (name "Net-(U1-QSPI_SCLK)") (class "Default")
      (node (ref "U1") (pin "56") (pinfunction "QSPI_SCLK_56") (pintype "unspecified"))
      (node (ref "U2") (pin "6") (pinfunction "CLK_6") (pintype "unspecified"))
    )
    (net (code "36") (name "Net-(U1-QSPI_SD0)") (class "Default")
      (node (ref "U1") (pin "57") (pinfunction "QSPI_SD0_57") (pintype "unspecified"))
      (node (ref "U2") (pin "5") (pinfunction "DI(IO0)_5") (pintype "unspecified"))
    )
    (net (code "37") (name "Net-(U1-QSPI_SD1)") (class "Default")
      (node (ref "U1") (pin "59") (pinfunction "QSPI_SD1_59") (pintype "unspecified"))
      (node (ref "U2") (pin "2") (pinfunction "DO(IO1)_2") (pintype "unspecified"))
    )
    (net (code "38") (name "Net-(U1-QSPI_SD2)") (class "Default")
      (node (ref "U1") (pin "58") (pinfunction "QSPI_SD2_58") (pintype "unspecified"))
      (node (ref "U2") (pin "3") (pinfunction "/WP(IO2)_3") (pintype "unspecified"))
    )
    (net (code "39") (name "Net-(U1-QSPI_SD3)") (class "Default")
      (node (ref "U1") (pin "55") (pinfunction "QSPI_SD3_55") (pintype "unspecified"))
      (node (ref "U2") (pin "7") (pinfunction "/HOLD/RESET(IO3)_7") (pintype "unspecified"))
    )
    (net (code "40") (name "Net-(U1-QSPI_SS)") (class "Default")
      (node (ref "R7") (pin "1") (pinfunction "1_1") (pintype "unspecified"))
      (node (ref "U1") (pin "60") (pinfunction "QSPI_SS_60") (pintype "unspecified"))
      (node (ref "U2") (pin "1") (pinfunction "/CS_1") (pintype "unspecified"))
    )
    (net (code "41") (name "Net-(U1-RUN)") (class "Default")
      (node (ref "R1") (pin "1") (pinfunction "1_1") (pintype "unspecified"))
      (node (ref "R2") (pin "1") (pinfunction "1_1") (pintype "unspecified"))
      (node (ref "U1") (pin "26") (pinfunction "RUN_26") (pintype "unspecified"))
    )
    (net (code "42") (name "Net-(U1-USB_DM)") (class "Default")
      (node (ref "R4") (pin "2") (pinfunction "2_2") (pintype "unspecified"))
      (node (ref "U1") (pin "51") (pinfunction "USB_DM_51") (pintype "unspecified"))
    )
    (net (code "43") (name "Net-(U1-USB_DP)") (class "Default")
      (node (ref "R5") (pin "2") (pinfunction "2_2") (pintype "unspecified"))
      (node (ref "U1") (pin "52") (pinfunction "USB_DP_52") (pintype "unspecified"))
    )
    (net (code "44") (name "Net-(U1-VREG_AVDD)") (class "Default")
      (node (ref "C3") (pin "1") (pinfunction "1_1") (pintype "input"))
      (node (ref "R3") (pin "1") (pinfunction "1_1") (pintype "unspecified"))
      (node (ref "U1") (pin "46") (pinfunction "VREG_AVDD_46") (pintype "unspecified"))
    )
    (net (code "45") (name "Net-(U1-VREG_LX)") (class "Default")
      (node (ref "L1") (pin "1") (pinfunction "1_1") (pintype "unspecified"))
      (node (ref "U1") (pin "48") (pinfunction "VREG_LX_48") (pintype "unspecified"))
    )
    (net (code "46") (name "Net-(U1-XIN)") (class "Default")
      (node (ref "C6") (pin "2") (pinfunction "2_2") (pintype "input"))
      (node (ref "U1") (pin "21") (pinfunction "XIN_21") (pintype "unspecified"))
      (node (ref "X1") (pin "1") (pinfunction "OSC1_1") (pintype "input"))
    )
    (net (code "47") (name "Net-(U1-XOUT)") (class "Default")
      (node (ref "R6") (pin "1") (pinfunction "1_1") (pintype "unspecified"))
      (node (ref "U1") (pin "22") (pinfunction "XOUT_22") (pintype "unspecified"))
    )
    (net (code "48") (name "Net-(U3-In)") (class "Default")
      (node (ref "C1") (pin "2") (pinfunction "2_2") (pintype "input"))
      (node (ref "F1") (pin "2") (pinfunction "2_2") (pintype "unspecified"))
      (node (ref "U3") (pin "3") (pinfunction "In_3") (pintype "unspecified"))
    )
    (net (code "49") (name "Net-(USB-A)") (class "Default")
      (node (ref "R10") (pin "2") (pinfunction "2_2") (pintype "unspecified"))
      (node (ref "USB") (pin "2") (pinfunction "A_2") (pintype "unspecified"))
    )
    (net (code "50") (name "Net-(USB1-D+)") (class "Default")
      (node (ref "R5") (pin "1") (pinfunction "1_1") (pintype "unspecified"))
      (node (ref "USB1") (pin "3") (pinfunction "D+_3") (pintype "input"))
    )
    (net (code "51") (name "Net-(USB1-D-)") (class "Default")
      (node (ref "R4") (pin "1") (pinfunction "1_1") (pintype "unspecified"))
      (node (ref "USB1") (pin "2") (pinfunction "D-_2") (pintype "input"))
    )
    (net (code "52") (name "Net-(X1-OSC2)") (class "Default")
      (node (ref "C7") (pin "2") (pinfunction "2_2") (pintype "input"))
      (node (ref "R6") (pin "2") (pinfunction "2_2") (pintype "unspecified"))
      (node (ref "X1") (pin "3") (pinfunction "OSC2_3") (pintype "input"))
    )
    (net (code "53") (name "gpio00") (class "Default")
      (node (ref "H1") (pin "14") (pinfunction "14_14") (pintype "unspecified"))
      (node (ref "RX1") (pin "1") (pinfunction "K_1") (pintype "unspecified"))
      (node (ref "U1") (pin "2") (pinfunction "GPIO0_2") (pintype "unspecified"))
    )
    (net (code "54") (name "gpio01") (class "Default")
      (node (ref "H1") (pin "13") (pinfunction "13_13") (pintype "unspecified"))
      (node (ref "TX1") (pin "1") (pinfunction "K_1") (pintype "unspecified"))
      (node (ref "U1") (pin "3") (pinfunction "GPIO1_3") (pintype "unspecified"))
    )
    (net (code "55") (name "gpio16") (class "Default")
      (node (ref "H1") (pin "5") (pinfunction "5_5") (pintype "unspecified"))
      (node (ref "U1") (pin "27") (pinfunction "GPIO16_27") (pintype "unspecified"))
    )
    (net (code "56") (name "gpio17") (class "Default")
      (node (ref "H1") (pin "6") (pinfunction "6_6") (pintype "unspecified"))
      (node (ref "U1") (pin "28") (pinfunction "GPIO17_28") (pintype "unspecified"))
    )
    (net (code "57") (name "gpio18") (class "Default")
      (node (ref "H1") (pin "7") (pinfunction "7_7") (pintype "unspecified"))
      (node (ref "U1") (pin "29") (pinfunction "GPIO18_29") (pintype "unspecified"))
    )
    (net (code "58") (name "gpio19") (class "Default")
      (node (ref "H1") (pin "8") (pinfunction "8_8") (pintype "unspecified"))
      (node (ref "U1") (pin "31") (pinfunction "GPIO19_31") (pintype "unspecified"))
    )
    (net (code "59") (name "gpio20") (class "Default")
      (node (ref "I2C") (pin "4") (pinfunction "4_4") (pintype "bidirectional"))
      (node (ref "R16") (pin "1") (pinfunction "1_1") (pintype "unspecified"))
      (node (ref "U1") (pin "32") (pinfunction "GPIO20_32") (pintype "unspecified"))
      (node (ref "U4") (pin "5") (pinfunction "SDA_5") (pintype "unspecified"))
    )
    (net (code "60") (name "gpio21") (class "Default")
      (node (ref "I2C") (pin "3") (pinfunction "3_3") (pintype "bidirectional"))
      (node (ref "R17") (pin "1") (pinfunction "1_1") (pintype "unspecified"))
      (node (ref "U1") (pin "33") (pinfunction "GPIO21_33") (pintype "unspecified"))
      (node (ref "U4") (pin "6") (pinfunction "SCL_6") (pintype "unspecified"))
    )
    (net (code "61") (name "gpio22") (class "Default")
      (node (ref "H1") (pin "9") (pinfunction "9_9") (pintype "unspecified"))
      (node (ref "U1") (pin "34") (pinfunction "GPIO22_34") (pintype "unspecified"))
    )
    (net (code "62") (name "gpio24") (class "Default")
      (node (ref "H1") (pin "10") (pinfunction "10_10") (pintype "unspecified"))
      (node (ref "U1") (pin "36") (pinfunction "GPIO24_36") (pintype "unspecified"))
    )
    (net (code "63") (name "gpio27") (class "Default")
      (node (ref "H1") (pin "11") (pinfunction "11_11") (pintype "unspecified"))
      (node (ref "U1") (pin "41") (pinfunction "GPIO27_ADC1_41") (pintype "unspecified"))
    )
    (net (code "64") (name "gpio28") (class "Default")
      (node (ref "H1") (pin "12") (pinfunction "12_12") (pintype "unspecified"))
      (node (ref "U1") (pin "42") (pinfunction "GPIO28_ADC2_42") (pintype "unspecified"))
    )
    (net (code "65") (name "swclk") (class "Default")
      (node (ref "DEBUG") (pin "3") (pinfunction "3_3") (pintype "input"))
      (node (ref "U1") (pin "24") (pinfunction "SWCLK_24") (pintype "unspecified"))
    )
    (net (code "66") (name "swdio") (class "Default")
      (node (ref "DEBUG") (pin "1") (pinfunction "1_1") (pintype "input"))
      (node (ref "U1") (pin "25") (pinfunction "SWDIO_25") (pintype "unspecified"))
    )
    (net (code "67") (name "unconnected-(BTN1-Pad1)") (class "Default")
      (node (ref "BTN1") (pin "1") (pinfunction "1_1") (pintype "unspecified"))
    )
    (net (code "68") (name "unconnected-(BTN1-Pad4)") (class "Default")
      (node (ref "BTN1") (pin "4") (pinfunction "4_4") (pintype "unspecified"))
    )
    (net (code "69") (name "unconnected-(BTN2-Pad1)") (class "Default")
      (node (ref "BTN2") (pin "1") (pinfunction "1_1") (pintype "unspecified"))
    )
    (net (code "70") (name "unconnected-(BTN2-Pad4)") (class "Default")
      (node (ref "BTN2") (pin "4") (pinfunction "4_4") (pintype "unspecified"))
    )
    (net (code "71") (name "unconnected-(BTN3-Pad1)") (class "Default")
      (node (ref "BTN3") (pin "1") (pinfunction "1_1") (pintype "unspecified"))
    )
    (net (code "72") (name "unconnected-(BTN3-Pad4)") (class "Default")
      (node (ref "BTN3") (pin "4") (pinfunction "4_4") (pintype "unspecified"))
    )
    (net (code "73") (name "unconnected-(U1-GPIO29_ADC3-Pad43)") (class "Default")
      (node (ref "U1") (pin "43") (pinfunction "GPIO29_ADC3_43") (pintype "unspecified"))
    )
    (net (code "74") (name "unconnected-(U5-NC-Pad9)") (class "Default")
      (node (ref "U5") (pin "9") (pinfunction "NC_9") (pintype "unspecified"))
    )
    (net (code "75") (name "unconnected-(U6-Pad1)") (class "Default")
      (node (ref "U6") (pin "1") (pinfunction "1_1") (pintype "unspecified"))
    )
    (net (code "76") (name "unconnected-(U6-Pad8)") (class "Default")
      (node (ref "U6") (pin "8") (pinfunction "8_8") (pintype "unspecified"))
    )
    (net (code "77") (name "unconnected-(USB1-ID-Pad4)") (class "Default")
      (node (ref "USB1") (pin "4") (pinfunction "ID_4") (pintype "input"))
    )
  )
)
